# Sheet2.net
KiCad netlist of a schematic drawn in Altium Designer
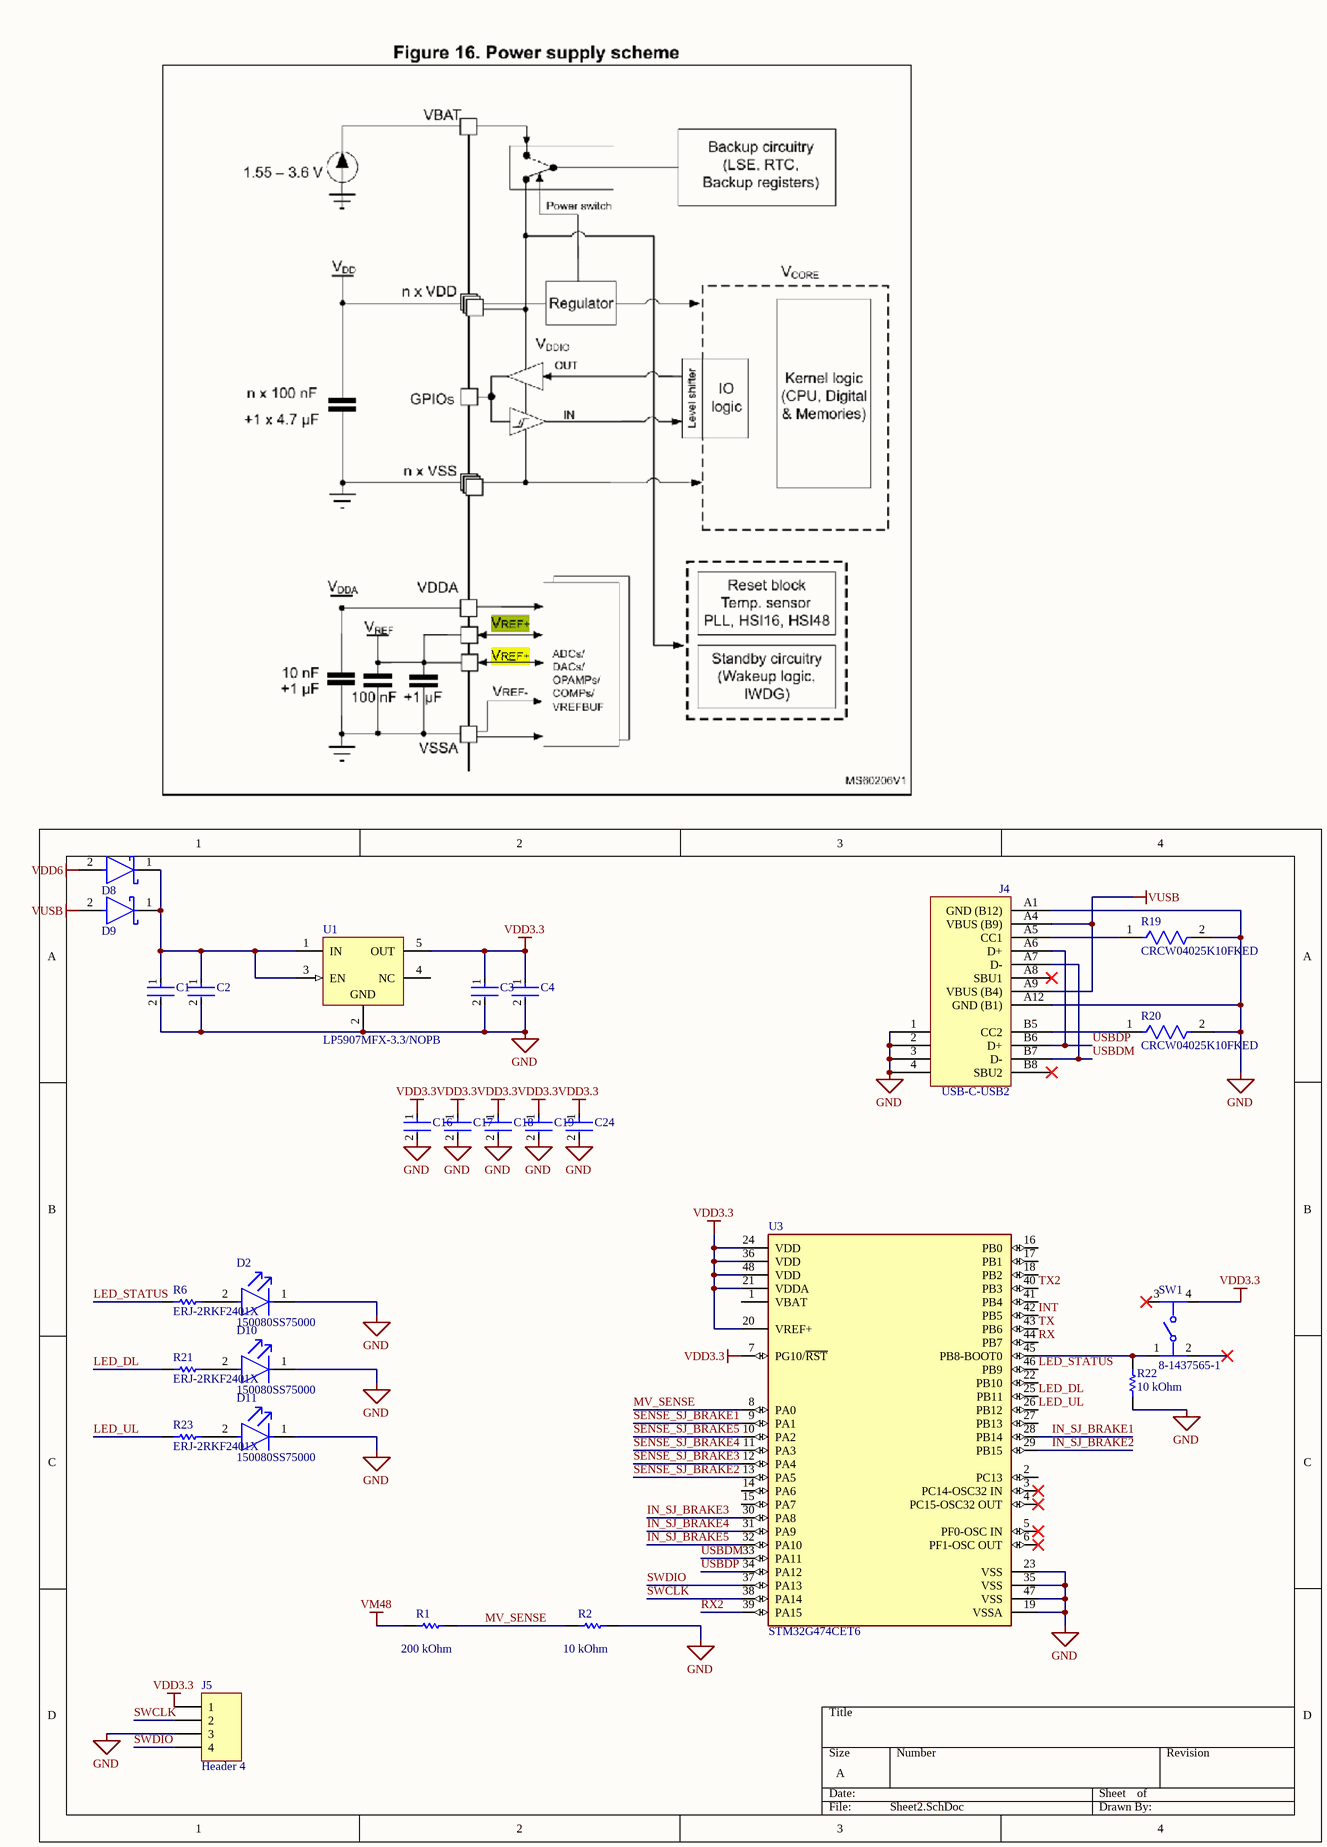
[diagram p0: Sheet2.SchDoc]

(export (version "E")
  (design (tool "Eeschema 10.0.6"))
  (components
    (comp (ref "C1")
      (value "C0603C225K4PACTU")
      (footprint "FP-C0603C225K4PACTU-MFG")
      (description "CAP CER 2.2UF 16V X5R 0603")
      (fields (field (name "TOLERANCE") "10%") (field (name "VOLTAGE") "16V"))
      (libsource (lib "Altium Content Vault") (part "b4654b650e69147ec39a6b967a45e02"))
    )
    (comp (ref "C2")
      (value "C0603C225K4PACTU")
      (footprint "FP-C0603C225K4PACTU-MFG")
      (description "CAP CER 2.2UF 16V X5R 0603")
      (fields (field (name "TOLERANCE") "10%") (field (name "VOLTAGE") "16V"))
      (libsource (lib "Altium Content Vault") (part "b4654b650e69147ec39a6b967a45e02"))
    )
    (comp (ref "C3")
      (value "C0603C225K4PACTU")
      (footprint "FP-C0603C225K4PACTU-MFG")
      (description "CAP CER 2.2UF 16V X5R 0603")
      (fields (field (name "TOLERANCE") "10%") (field (name "VOLTAGE") "16V"))
      (libsource (lib "Altium Content Vault") (part "b4654b650e69147ec39a6b967a45e02"))
    )
    (comp (ref "C4")
      (value "C0603C225K4PACTU")
      (footprint "FP-C0603C225K4PACTU-MFG")
      (description "CAP CER 2.2UF 16V X5R 0603")
      (fields (field (name "TOLERANCE") "10%") (field (name "VOLTAGE") "16V"))
      (libsource (lib "Altium Content Vault") (part "b4654b650e69147ec39a6b967a45e02"))
    )
    (comp (ref "C16")
      (value "C0603C225K4PACTU")
      (footprint "FP-C0603C225K4PACTU-MFG")
      (description "CAP CER 2.2UF 16V X5R 0603")
      (fields (field (name "TOLERANCE") "10%") (field (name "VOLTAGE") "16V"))
      (libsource (lib "Altium Content Vault") (part "b4654b650e69147ec39a6b967a45e02"))
    )
    (comp (ref "C17")
      (value "C0603C225K4PACTU")
      (footprint "FP-C0603C225K4PACTU-MFG")
      (description "CAP CER 2.2UF 16V X5R 0603")
      (fields (field (name "TOLERANCE") "10%") (field (name "VOLTAGE") "16V"))
      (libsource (lib "Altium Content Vault") (part "b4654b650e69147ec39a6b967a45e02"))
    )
    (comp (ref "C18")
      (value "C0603C225K4PACTU")
      (footprint "FP-C0603C225K4PACTU-MFG")
      (description "CAP CER 2.2UF 16V X5R 0603")
      (fields (field (name "TOLERANCE") "10%") (field (name "VOLTAGE") "16V"))
      (libsource (lib "Altium Content Vault") (part "b4654b650e69147ec39a6b967a45e02"))
    )
    (comp (ref "C19")
      (value "C0603C225K4PACTU")
      (footprint "FP-C0603C225K4PACTU-MFG")
      (description "CAP CER 2.2UF 16V X5R 0603")
      (fields (field (name "TOLERANCE") "10%") (field (name "VOLTAGE") "16V"))
      (libsource (lib "Altium Content Vault") (part "b4654b650e69147ec39a6b967a45e02"))
    )
    (comp (ref "C24")
      (value "C0603C225K4PACTU")
      (footprint "FP-C0603C225K4PACTU-MFG")
      (description "CAP CER 2.2UF 16V X5R 0603")
      (fields (field (name "TOLERANCE") "10%") (field (name "VOLTAGE") "16V"))
      (libsource (lib "Altium Content Vault") (part "b4654b650e69147ec39a6b967a45e02"))
    )
    (comp (ref "D2")
      (value "150080SS75000")
      (footprint "FP-150080SS75000-MFG")
      (description "LED RED CLEAR 0805 SMD")
      (libsource (lib "Altium Content Vault") (part "8706943c75ba83719d021d2fdc84c58"))
    )
    (comp (ref "D8")
      (value "VS-10MQ100NTRPBF")
      (footprint "FP-95400-MFG")
      (description "DIODE SCHOTTKY 100V 1A SMA")
      (fields
        (field (name "OCTOPART") "https://octopart.com/vs-10mq100ntrpbf-vishay-44340924")
        (field (name "MANUFACTURER") "Vishay")
      )
      (libsource (lib "Altium Content Vault") (part "c1678fac7984e62e0809fbf79c06691"))
    )
    (comp (ref "D9")
      (value "VS-10MQ100NTRPBF")
      (footprint "FP-95400-MFG")
      (description "DIODE SCHOTTKY 100V 1A SMA")
      (fields
        (field (name "OCTOPART") "https://octopart.com/vs-10mq100ntrpbf-vishay-44340924")
        (field (name "MANUFACTURER") "Vishay")
      )
      (libsource (lib "Altium Content Vault") (part "c1678fac7984e62e0809fbf79c06691"))
    )
    (comp (ref "D10")
      (value "150080SS75000")
      (footprint "FP-150080SS75000-MFG")
      (description "LED RED CLEAR 0805 SMD")
      (libsource (lib "Altium Content Vault") (part "8706943c75ba83719d021d2fdc84c58"))
    )
    (comp (ref "D11")
      (value "150080SS75000")
      (footprint "FP-150080SS75000-MFG")
      (description "LED RED CLEAR 0805 SMD")
      (libsource (lib "Altium Content Vault") (part "8706943c75ba83719d021d2fdc84c58"))
    )
    (comp (ref "J4")
      (value "USB-C-USB2")
      (footprint "USB-C-USB4105")
      (fields (field (name "MP") "USB4105") (field (name "MF") "Global Connector Technology"))
      (libsource (lib "dvrk-fixture") (part "USB-C-USB2"))
    )
    (comp (ref "J5")
      (value "Header 4")
      (footprint "HDR1X4")
      (description "Header, 4-Pin")
      (fields (field (name "PUBLISHER") "Altium Limited"))
      (libsource (lib "Miscellaneous Connectors") (part "Header 4"))
    )
    (comp (ref "R1")
      (value "200 kOhm")
      (footprint "RESC1005X40X25LL05T10")
      (fields (field (name "PART NUMBER") "RC0402FR-07200KL") (field (name "MANUFACTURER") "Yageo / Phycomp"))
      (libsource (lib "Altium Content Vault") (part "RES"))
    )
    (comp (ref "R2")
      (value "10 kOhm")
      (footprint "RESC1005X40X25LL05T10")
      (fields (field (name "PART NUMBER") "RC0402FR-0710KL") (field (name "MANUFACTURER") "Yageo / Phycomp"))
      (libsource (lib "Altium Content Vault") (part "RES"))
    )
    (comp (ref "R6")
      (value "ERJ-2RKF2401X")
      (footprint "RESC1005X40X25LL05T05")
      (fields (field (name "MANUFACTURER") "Panasonic"))
      (libsource (lib "Altium Content Vault") (part "RES"))
    )
    (comp (ref "R19")
      (value "CRCW04025K10FKED")
      (footprint "FP-CRCW0402-e3-IPC_C")
      (description "RES Thick Film, 5.1kΩ, 1%, 0.063W, 100ppm/°C, 0402")
      (fields (field (name "TOLERANCE") "1%"))
      (libsource (lib "Altium Content Vault") (part "1029c3af85768c4190bb7ad29bc67b5"))
    )
    (comp (ref "R20")
      (value "CRCW04025K10FKED")
      (footprint "FP-CRCW0402-e3-IPC_C")
      (description "RES Thick Film, 5.1kΩ, 1%, 0.063W, 100ppm/°C, 0402")
      (fields (field (name "TOLERANCE") "1%"))
      (libsource (lib "Altium Content Vault") (part "1029c3af85768c4190bb7ad29bc67b5"))
    )
    (comp (ref "R21")
      (value "ERJ-2RKF2401X")
      (footprint "RESC1005X40X25LL05T05")
      (fields (field (name "MANUFACTURER") "Panasonic"))
      (libsource (lib "Altium Content Vault") (part "RES"))
    )
    (comp (ref "R22")
      (value "10 kOhm")
      (footprint "RESC1005X40X25LL05T10")
      (fields (field (name "PART NUMBER") "RC0402FR-0710KL") (field (name "MANUFACTURER") "Yageo / Phycomp"))
      (libsource (lib "Altium Content Vault") (part "RES"))
    )
    (comp (ref "R23")
      (value "ERJ-2RKF2401X")
      (footprint "RESC1005X40X25LL05T05")
      (fields (field (name "MANUFACTURER") "Panasonic"))
      (libsource (lib "Altium Content Vault") (part "RES"))
    )
    (comp (ref "SW1")
      (value "8-1437565-1")
      (footprint "FP-8-1437565-1-MFG")
      (description "SWITCH TACTILE SPST-NO 0.02A 15V")
      (libsource (lib "Altium Content Vault") (part "b8895f3f4cefb76e1819d2863dba89b"))
    )
    (comp (ref "U1")
      (value "LP5907MFX-3.3/NOPB")
      (footprint "DBV0005A_N")
      (description "None")
      (libsource (lib "Altium Content Vault") (part "TI-LP5907-SOT-23-5"))
    )
    (comp (ref "U3")
      (value "STM32G474CET6")
      (footprint "FP-STM32G474CET6-MFG")
      (description "MAINSTREAM ARM CORTEX-M4 CORE WI")
      (fields
        (field (name "OCTOPART") "https://octopart.com/stm32g474cet6-stmicroelectronics-99072248")
        (field (name "MANUFACTURER") "STMicroelectronics")
      )
      (libsource (lib "Altium Content Vault") (part "96d063d3108c84c79c2ea684d87d0dc"))
    )
  )
  (nets
    (net (code "1") (name "/INT") (class "Default")
      (node (ref "U3") (pin "42") (pinfunction "PB5_42") (pintype "bidirectional"))
    )
    (net (code "2") (name "/IN_SJ_BRAKE1") (class "Default")
      (node (ref "U3") (pin "28") (pinfunction "PB14_28") (pintype "bidirectional"))
    )
    (net (code "3") (name "/IN_SJ_BRAKE2") (class "Default")
      (node (ref "U3") (pin "29") (pinfunction "PB15_29") (pintype "bidirectional"))
    )
    (net (code "4") (name "/IN_SJ_BRAKE3") (class "Default")
      (node (ref "U3") (pin "30") (pinfunction "PA8_30") (pintype "bidirectional"))
    )
    (net (code "5") (name "/IN_SJ_BRAKE4") (class "Default")
      (node (ref "U3") (pin "31") (pinfunction "PA9_31") (pintype "bidirectional"))
    )
    (net (code "6") (name "/IN_SJ_BRAKE5") (class "Default")
      (node (ref "U3") (pin "32") (pinfunction "PA10_32") (pintype "bidirectional"))
    )
    (net (code "7") (name "/LED_DL") (class "Default")
      (node (ref "R21") (pin "1") (pinfunction "1_1") (pintype "passive"))
      (node (ref "U3") (pin "25") (pinfunction "PB11_25") (pintype "bidirectional"))
    )
    (net (code "8") (name "/LED_STATUS") (class "Default")
      (node (ref "R6") (pin "1") (pinfunction "1_1") (pintype "passive"))
      (node (ref "U3") (pin "46") (pinfunction "PB9_46") (pintype "bidirectional"))
    )
    (net (code "9") (name "/LED_UL") (class "Default")
      (node (ref "R23") (pin "1") (pinfunction "1_1") (pintype "passive"))
      (node (ref "U3") (pin "26") (pinfunction "PB12_26") (pintype "bidirectional"))
    )
    (net (code "10") (name "/MV_SENSE") (class "Default")
      (node (ref "R1") (pin "2") (pinfunction "2_2") (pintype "passive"))
      (node (ref "R2") (pin "1") (pinfunction "1_1") (pintype "passive"))
      (node (ref "U3") (pin "8") (pinfunction "PA0_8") (pintype "bidirectional"))
    )
    (net (code "11") (name "/RX") (class "Default")
      (node (ref "U3") (pin "44") (pinfunction "PB7_44") (pintype "bidirectional"))
    )
    (net (code "12") (name "/RX2") (class "Default")
      (node (ref "U3") (pin "39") (pinfunction "PA15_39") (pintype "bidirectional"))
    )
    (net (code "13") (name "/SENSE_SJ_BRAKE1") (class "Default")
      (node (ref "U3") (pin "9") (pinfunction "PA1_9") (pintype "bidirectional"))
    )
    (net (code "14") (name "/SENSE_SJ_BRAKE2") (class "Default")
      (node (ref "U3") (pin "13") (pinfunction "PA5_13") (pintype "bidirectional"))
    )
    (net (code "15") (name "/SENSE_SJ_BRAKE3") (class "Default")
      (node (ref "U3") (pin "12") (pinfunction "PA4_12") (pintype "bidirectional"))
    )
    (net (code "16") (name "/SENSE_SJ_BRAKE4") (class "Default")
      (node (ref "U3") (pin "11") (pinfunction "PA3_11") (pintype "bidirectional"))
    )
    (net (code "17") (name "/SENSE_SJ_BRAKE5") (class "Default")
      (node (ref "U3") (pin "10") (pinfunction "PA2_10") (pintype "bidirectional"))
    )
    (net (code "18") (name "/SWCLK") (class "Default")
      (node (ref "J5") (pin "2") (pinfunction "2_2") (pintype "passive"))
      (node (ref "U3") (pin "38") (pinfunction "PA14_38") (pintype "bidirectional"))
    )
    (net (code "19") (name "/SWDIO") (class "Default")
      (node (ref "J5") (pin "4") (pinfunction "4_4") (pintype "passive"))
      (node (ref "U3") (pin "37") (pinfunction "PA13_37") (pintype "bidirectional"))
    )
    (net (code "20") (name "/TX") (class "Default")
      (node (ref "U3") (pin "43") (pinfunction "PB6_43") (pintype "bidirectional"))
    )
    (net (code "21") (name "/TX2") (class "Default")
      (node (ref "U3") (pin "40") (pinfunction "PB3_40") (pintype "bidirectional"))
    )
    (net (code "22") (name "/USBDM") (class "Default")
      (node (ref "J4") (pin "A7") (pinfunction "D-_A7") (pintype "passive"))
      (node (ref "J4") (pin "B7") (pinfunction "D-_B7") (pintype "passive"))
      (node (ref "U3") (pin "33") (pinfunction "PA11_33") (pintype "bidirectional"))
    )
    (net (code "23") (name "/USBDP") (class "Default")
      (node (ref "J4") (pin "A6") (pinfunction "D+_A6") (pintype "passive"))
      (node (ref "J4") (pin "B6") (pinfunction "D+_B6") (pintype "passive"))
      (node (ref "U3") (pin "34") (pinfunction "PA12_34") (pintype "bidirectional"))
    )
    (net (code "24") (name "GND") (class "Default")
      (node (ref "C1") (pin "2") (pinfunction "2_2") (pintype "passive"))
      (node (ref "C16") (pin "2") (pinfunction "2_2") (pintype "passive"))
      (node (ref "C17") (pin "2") (pinfunction "2_2") (pintype "passive"))
      (node (ref "C18") (pin "2") (pinfunction "2_2") (pintype "passive"))
      (node (ref "C19") (pin "2") (pinfunction "2_2") (pintype "passive"))
      (node (ref "C2") (pin "2") (pinfunction "2_2") (pintype "passive"))
      (node (ref "C24") (pin "2") (pinfunction "2_2") (pintype "passive"))
      (node (ref "C3") (pin "2") (pinfunction "2_2") (pintype "passive"))
      (node (ref "C4") (pin "2") (pinfunction "2_2") (pintype "passive"))
      (node (ref "D10") (pin "1") (pinfunction "C_1") (pintype "passive"))
      (node (ref "D11") (pin "1") (pinfunction "C_1") (pintype "passive"))
      (node (ref "D2") (pin "1") (pinfunction "C_1") (pintype "passive"))
      (node (ref "J4") (pin "1") (pinfunction "CHASIS_1") (pintype "power_in"))
      (node (ref "J4") (pin "2") (pinfunction "CHASIS_2") (pintype "power_in"))
      (node (ref "J4") (pin "3") (pinfunction "CHASIS_3") (pintype "power_in"))
      (node (ref "J4") (pin "4") (pinfunction "CHASIS_4") (pintype "power_in"))
      (node (ref "J4") (pin "A1") (pinfunction "GND_(B12)_A1") (pintype "passive"))
      (node (ref "J4") (pin "A12") (pinfunction "GND_(B1)_A12") (pintype "passive"))
      (node (ref "J5") (pin "3") (pinfunction "3_3") (pintype "passive"))
      (node (ref "R19") (pin "2") (pinfunction "2_2") (pintype "passive"))
      (node (ref "R2") (pin "2") (pinfunction "2_2") (pintype "passive"))
      (node (ref "R20") (pin "2") (pinfunction "2_2") (pintype "passive"))
      (node (ref "R22") (pin "1") (pinfunction "1_1") (pintype "passive"))
      (node (ref "U1") (pin "2") (pinfunction "GND_2") (pintype "power_in"))
      (node (ref "U3") (pin "19") (pinfunction "VSSA_19") (pintype "power_in"))
      (node (ref "U3") (pin "23") (pinfunction "VSS_23") (pintype "power_in"))
      (node (ref "U3") (pin "35") (pinfunction "VSS_35") (pintype "power_in"))
      (node (ref "U3") (pin "47") (pinfunction "VSS_47") (pintype "power_in"))
    )
    (net (code "25") (name "Net-(D2-A)") (class "Default")
      (node (ref "D2") (pin "2") (pinfunction "A_2") (pintype "passive"))
      (node (ref "R6") (pin "2") (pinfunction "2_2") (pintype "passive"))
    )
    (net (code "26") (name "Net-(D8-C)") (class "Default")
      (node (ref "C1") (pin "1") (pinfunction "1_1") (pintype "passive"))
      (node (ref "C2") (pin "1") (pinfunction "1_1") (pintype "passive"))
      (node (ref "D8") (pin "1") (pinfunction "C_1") (pintype "passive"))
      (node (ref "D9") (pin "1") (pinfunction "C_1") (pintype "passive"))
      (node (ref "U1") (pin "1") (pinfunction "IN_1") (pintype "power_in"))
      (node (ref "U1") (pin "3") (pinfunction "EN_3") (pintype "input"))
    )
    (net (code "27") (name "Net-(D10-A)") (class "Default")
      (node (ref "D10") (pin "2") (pinfunction "A_2") (pintype "passive"))
      (node (ref "R21") (pin "2") (pinfunction "2_2") (pintype "passive"))
    )
    (net (code "28") (name "Net-(D11-A)") (class "Default")
      (node (ref "D11") (pin "2") (pinfunction "A_2") (pintype "passive"))
      (node (ref "R23") (pin "2") (pinfunction "2_2") (pintype "passive"))
    )
    (net (code "29") (name "Net-(J4-CC1)") (class "Default")
      (node (ref "J4") (pin "A5") (pinfunction "CC1_A5") (pintype "passive"))
      (node (ref "R19") (pin "1") (pinfunction "1_1") (pintype "passive"))
    )
    (net (code "30") (name "Net-(J4-CC2)") (class "Default")
      (node (ref "J4") (pin "B5") (pinfunction "CC2_B5") (pintype "passive"))
      (node (ref "R20") (pin "1") (pinfunction "1_1") (pintype "passive"))
    )
    (net (code "31") (name "Net-(U3-PB8-BOOT0)") (class "Default")
      (node (ref "R22") (pin "2") (pinfunction "2_2") (pintype "passive"))
      (node (ref "SW1") (pin "1") (pinfunction "1_1") (pintype "passive"))
      (node (ref "U3") (pin "45") (pinfunction "PB8-BOOT0_45") (pintype "bidirectional"))
    )
    (net (code "32") (name "VDD3.3") (class "Default")
      (node (ref "C16") (pin "1") (pinfunction "1_1") (pintype "passive"))
      (node (ref "C17") (pin "1") (pinfunction "1_1") (pintype "passive"))
      (node (ref "C18") (pin "1") (pinfunction "1_1") (pintype "passive"))
      (node (ref "C19") (pin "1") (pinfunction "1_1") (pintype "passive"))
      (node (ref "C24") (pin "1") (pinfunction "1_1") (pintype "passive"))
      (node (ref "C3") (pin "1") (pinfunction "1_1") (pintype "passive"))
      (node (ref "C4") (pin "1") (pinfunction "1_1") (pintype "passive"))
      (node (ref "J5") (pin "1") (pinfunction "1_1") (pintype "passive"))
      (node (ref "SW1") (pin "4") (pinfunction "4_4") (pintype "passive"))
      (node (ref "U1") (pin "5") (pinfunction "OUT_5") (pintype "power_in"))
      (node (ref "U3") (pin "20") (pinfunction "VREF+_20") (pintype "power_in"))
      (node (ref "U3") (pin "21") (pinfunction "VDDA_21") (pintype "power_in"))
      (node (ref "U3") (pin "24") (pinfunction "VDD_24") (pintype "power_in"))
      (node (ref "U3") (pin "36") (pinfunction "VDD_36") (pintype "power_in"))
      (node (ref "U3") (pin "48") (pinfunction "VDD_48") (pintype "power_in"))
      (node (ref "U3") (pin "7") (pinfunction "PG10/~{RST}_7") (pintype "bidirectional"))
    )
    (net (code "33") (name "VDD6") (class "Default")
      (node (ref "D8") (pin "2") (pinfunction "A_2") (pintype "passive"))
    )
    (net (code "34") (name "VM48") (class "Default")
      (node (ref "R1") (pin "1") (pinfunction "1_1") (pintype "passive"))
    )
    (net (code "35") (name "VUSB") (class "Default")
      (node (ref "D9") (pin "2") (pinfunction "A_2") (pintype "passive"))
      (node (ref "J4") (pin "A4") (pinfunction "VBUS_(B9)_A4") (pintype "passive"))
      (node (ref "J4") (pin "A9") (pinfunction "VBUS_(B4)_A9") (pintype "passive"))
    )
    (net (code "36") (name "unconnected-(J4-SBU1-PadA8)") (class "Default")
      (node (ref "J4") (pin "A8") (pinfunction "SBU1_A8") (pintype "passive+no_connect"))
    )
    (net (code "37") (name "unconnected-(J4-SBU2-PadB8)") (class "Default")
      (node (ref "J4") (pin "B8") (pinfunction "SBU2_B8") (pintype "passive+no_connect"))
    )
    (net (code "38") (name "unconnected-(SW1-Pad2)") (class "Default")
      (node (ref "SW1") (pin "2") (pinfunction "2_2") (pintype "passive+no_connect"))
    )
    (net (code "39") (name "unconnected-(SW1-Pad3)") (class "Default")
      (node (ref "SW1") (pin "3") (pinfunction "3_3") (pintype "passive+no_connect"))
    )
    (net (code "40") (name "unconnected-(U1-NC-Pad4)") (class "Default")
      (node (ref "U1") (pin "4") (pinfunction "NC_4") (pintype "passive"))
    )
    (net (code "41") (name "unconnected-(U3-PA6-Pad14)") (class "Default")
      (node (ref "U3") (pin "14") (pinfunction "PA6_14") (pintype "bidirectional"))
    )
    (net (code "42") (name "unconnected-(U3-PA7-Pad15)") (class "Default")
      (node (ref "U3") (pin "15") (pinfunction "PA7_15") (pintype "bidirectional"))
    )
    (net (code "43") (name "unconnected-(U3-PB0-Pad16)") (class "Default")
      (node (ref "U3") (pin "16") (pinfunction "PB0_16") (pintype "bidirectional"))
    )
    (net (code "44") (name "unconnected-(U3-PB1-Pad17)") (class "Default")
      (node (ref "U3") (pin "17") (pinfunction "PB1_17") (pintype "bidirectional"))
    )
    (net (code "45") (name "unconnected-(U3-PB2-Pad18)") (class "Default")
      (node (ref "U3") (pin "18") (pinfunction "PB2_18") (pintype "bidirectional"))
    )
    (net (code "46") (name "unconnected-(U3-PB4-Pad41)") (class "Default")
      (node (ref "U3") (pin "41") (pinfunction "PB4_41") (pintype "bidirectional"))
    )
    (net (code "47") (name "unconnected-(U3-PB10-Pad22)") (class "Default")
      (node (ref "U3") (pin "22") (pinfunction "PB10_22") (pintype "bidirectional"))
    )
    (net (code "48") (name "unconnected-(U3-PB13-Pad27)") (class "Default")
      (node (ref "U3") (pin "27") (pinfunction "PB13_27") (pintype "bidirectional"))
    )
    (net (code "49") (name "unconnected-(U3-PC13-Pad2)") (class "Default")
      (node (ref "U3") (pin "2") (pinfunction "PC13_2") (pintype "bidirectional"))
    )
    (net (code "50") (name "unconnected-(U3-PC14-OSC32_IN-Pad3)") (class "Default")
      (node (ref "U3") (pin "3") (pinfunction "PC14-OSC32_IN_3") (pintype "bidirectional+no_connect"))
    )
    (net (code "51") (name "unconnected-(U3-PC15-OSC32_OUT-Pad4)") (class "Default")
      (node (ref "U3") (pin "4") (pinfunction "PC15-OSC32_OUT_4") (pintype "bidirectional+no_connect"))
    )
    (net (code "52") (name "unconnected-(U3-PF0-OSC_IN-Pad5)") (class "Default")
      (node (ref "U3") (pin "5") (pinfunction "PF0-OSC_IN_5") (pintype "bidirectional+no_connect"))
    )
    (net (code "53") (name "unconnected-(U3-PF1-OSC_OUT-Pad6)") (class "Default")
      (node (ref "U3") (pin "6") (pinfunction "PF1-OSC_OUT_6") (pintype "bidirectional+no_connect"))
    )
    (net (code "54") (name "unconnected-(U3-VBAT-Pad1)") (class "Default")
      (node (ref "U3") (pin "1") (pinfunction "VBAT_1") (pintype "power_in"))
    )
  )
)
